# Keg_Cop_-_RJ45.net
KiCad netlist of a schematic drawn in EAGLE
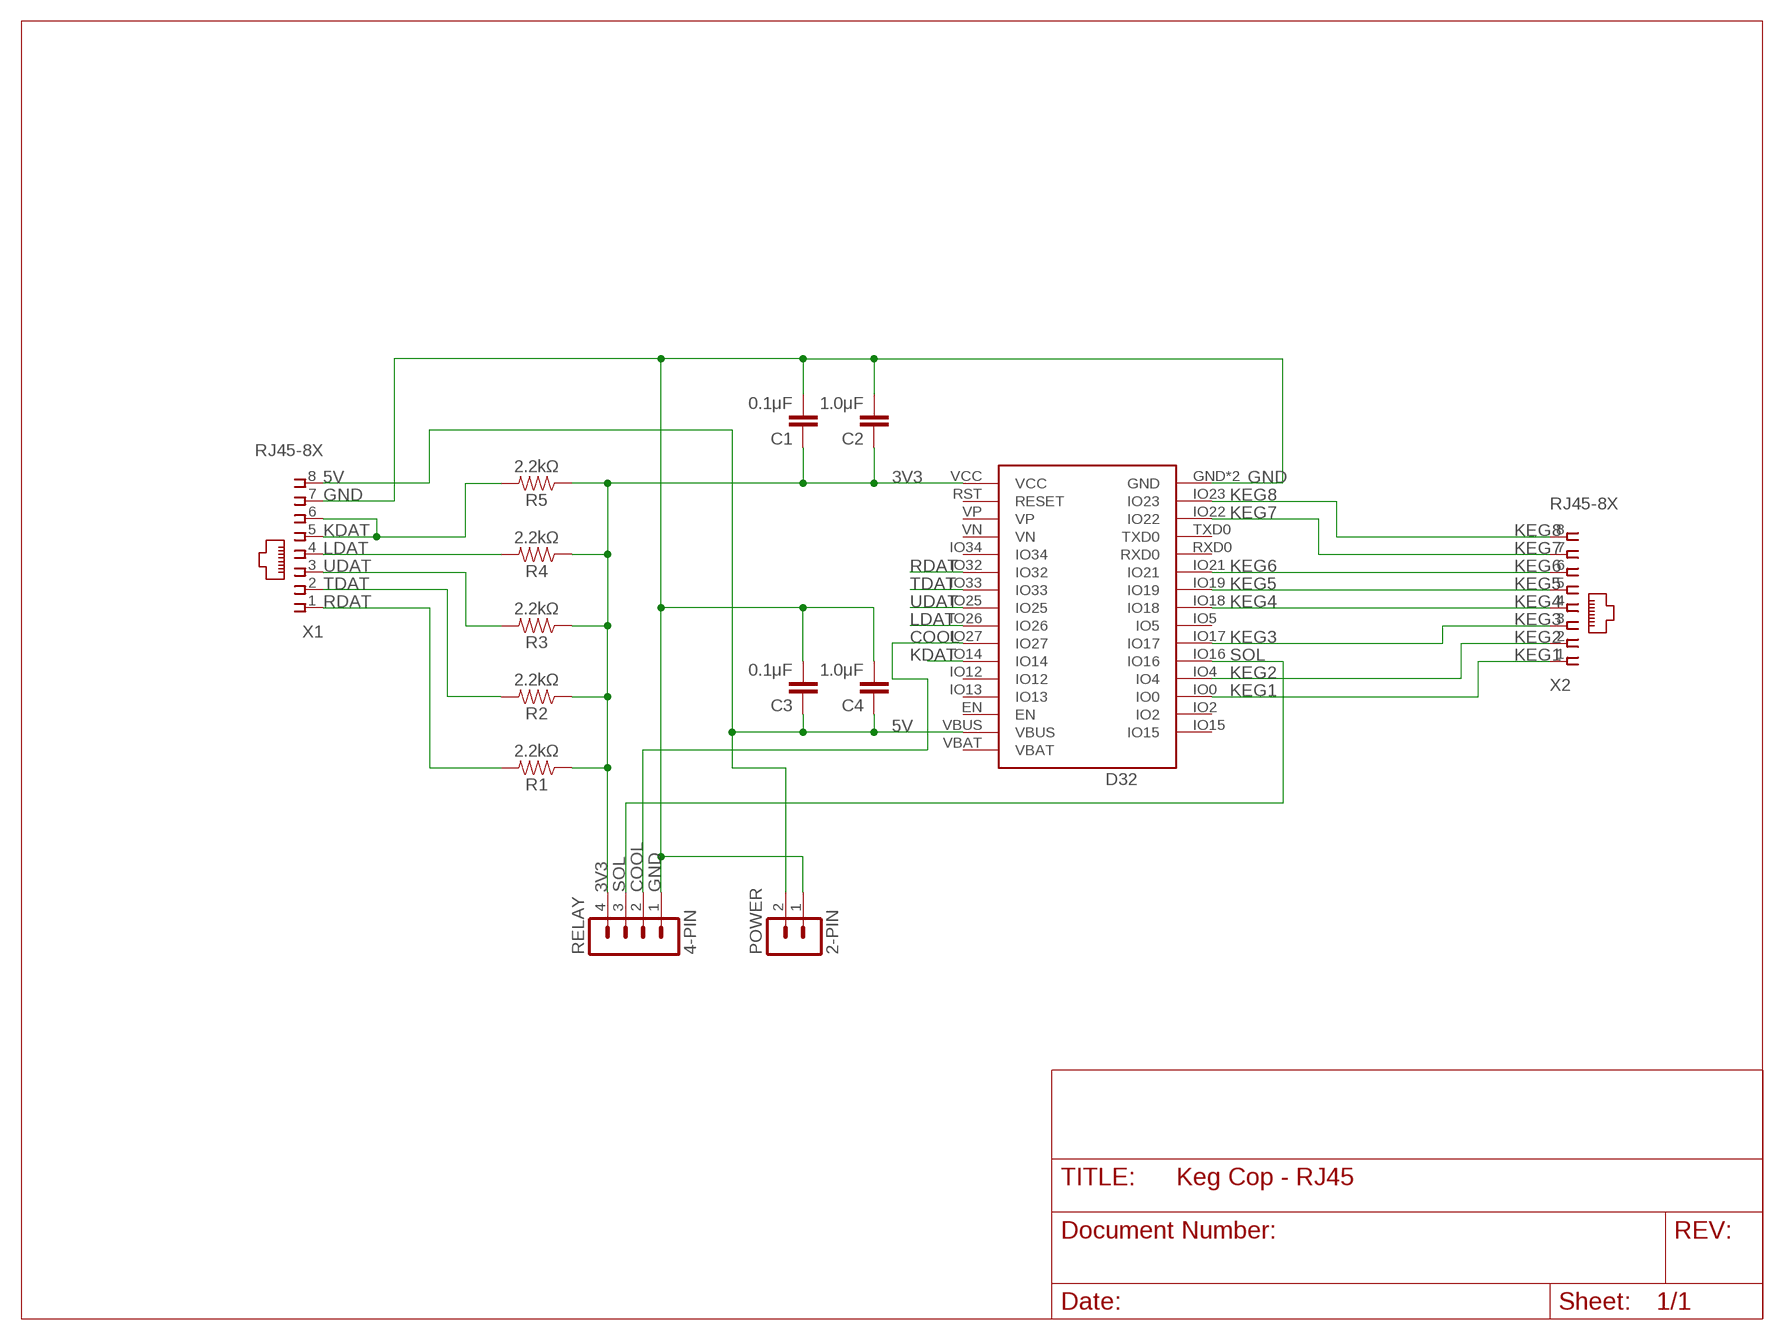
[diagram p0: schematic, sheet 1]

(export (version "E")
  (design (tool "Eeschema 10.0.6"))
  (components
    (comp (ref "C1")
      (value "0.1μF")
      (footprint "eagle-import:CAP_PTH-2.54")
      (libsource (lib "eagle-import") (part "CAP_CERAMIC_2.54"))
    )
    (comp (ref "C2")
      (value "1.0μF")
      (footprint "eagle-import:CAP_PTH-2.54")
      (libsource (lib "eagle-import") (part "CAP_CERAMIC_2.54"))
    )
    (comp (ref "C3")
      (value "0.1μF")
      (footprint "eagle-import:CAP_PTH-2.54")
      (libsource (lib "eagle-import") (part "CAP_CERAMIC_2.54"))
    )
    (comp (ref "C4")
      (value "1.0μF")
      (footprint "eagle-import:CAP_PTH-2.54")
      (libsource (lib "eagle-import") (part "CAP_CERAMIC_2.54"))
    )
    (comp (ref "D32")
      (value "Lolin D32")
      (footprint "eagle-import:D32_NO_BATT")
      (libsource (lib "eagle-import") (part "WEMOS-D32D32_NO_BATT"))
    )
    (comp (ref "POWER")
      (value "2-PIN")
      (footprint "eagle-import:HDR-2_VERT")
      (libsource (lib "eagle-import") (part "HDR-2"))
    )
    (comp (ref "R1")
      (value "2.2kΩ")
      (footprint "eagle-import:AXIAL-0.3")
      (libsource (lib "eagle-import") (part "RESISTORAXIAL-0.3"))
    )
    (comp (ref "R2")
      (value "2.2kΩ")
      (footprint "eagle-import:AXIAL-0.3")
      (libsource (lib "eagle-import") (part "RESISTORAXIAL-0.3"))
    )
    (comp (ref "R3")
      (value "2.2kΩ")
      (footprint "eagle-import:AXIAL-0.3")
      (libsource (lib "eagle-import") (part "RESISTORAXIAL-0.3"))
    )
    (comp (ref "R4")
      (value "2.2kΩ")
      (footprint "eagle-import:AXIAL-0.3")
      (libsource (lib "eagle-import") (part "RESISTORAXIAL-0.3"))
    )
    (comp (ref "R5")
      (value "2.2kΩ")
      (footprint "eagle-import:AXIAL-0.3")
      (libsource (lib "eagle-import") (part "RESISTORAXIAL-0.3"))
    )
    (comp (ref "RELAY")
      (value "4-PIN")
      (footprint "eagle-import:MA04-1")
      (libsource (lib "eagle-import") (part "MA04-1"))
    )
    (comp (ref "X1")
      (value "RJ45-8X")
      (footprint "eagle-import:RJ45-NO-SHIELD")
      (libsource (lib "eagle-import") (part "RJ45-8X"))
    )
    (comp (ref "X2")
      (value "RJ45-8X")
      (footprint "eagle-import:RJ45-NO-SHIELD")
      (libsource (lib "eagle-import") (part "RJ45-8X"))
    )
  )
  (nets
    (net (code "1") (name "/3V3") (class "Default")
      (node (ref "C1") (pin "1") (pinfunction "1_1") (pintype "passive"))
      (node (ref "C2") (pin "1") (pinfunction "1_1") (pintype "passive"))
      (node (ref "D32") (pin "VCC") (pinfunction "VCC_VCC") (pintype "power_in"))
      (node (ref "R1") (pin "P$1") (pinfunction "1_P$1") (pintype "passive"))
      (node (ref "R2") (pin "P$1") (pinfunction "1_P$1") (pintype "passive"))
      (node (ref "R3") (pin "P$1") (pinfunction "1_P$1") (pintype "passive"))
      (node (ref "R4") (pin "P$1") (pinfunction "1_P$1") (pintype "passive"))
      (node (ref "R5") (pin "P$1") (pinfunction "1_P$1") (pintype "passive"))
      (node (ref "RELAY") (pin "4") (pinfunction "4_4") (pintype "passive"))
    )
    (net (code "2") (name "/5V") (class "Default")
      (node (ref "C3") (pin "1") (pinfunction "1_1") (pintype "passive"))
      (node (ref "C4") (pin "1") (pinfunction "1_1") (pintype "passive"))
      (node (ref "D32") (pin "VBUS") (pinfunction "VBUS_VBUS") (pintype "bidirectional"))
      (node (ref "POWER") (pin "2") (pinfunction "2_2") (pintype "passive"))
      (node (ref "X1") (pin "8") (pinfunction "8_8") (pintype "passive"))
    )
    (net (code "3") (name "/COOL") (class "Default")
      (node (ref "D32") (pin "IO27") (pinfunction "IO27_IO27") (pintype "bidirectional"))
      (node (ref "RELAY") (pin "2") (pinfunction "2_2") (pintype "passive"))
    )
    (net (code "4") (name "/GND") (class "Default")
      (node (ref "C1") (pin "2") (pinfunction "2_2") (pintype "passive"))
      (node (ref "C2") (pin "2") (pinfunction "2_2") (pintype "passive"))
      (node (ref "C3") (pin "2") (pinfunction "2_2") (pintype "passive"))
      (node (ref "C4") (pin "2") (pinfunction "2_2") (pintype "passive"))
      (node (ref "D32") (pin "GND") (pinfunction "GND_GND") (pintype "power_in"))
      (node (ref "D32") (pin "GND2") (pinfunction "GND_GND2") (pintype "power_in"))
      (node (ref "POWER") (pin "1") (pinfunction "1_1") (pintype "passive"))
      (node (ref "RELAY") (pin "1") (pinfunction "1_1") (pintype "passive"))
      (node (ref "X1") (pin "7") (pinfunction "7_7") (pintype "passive"))
    )
    (net (code "5") (name "/KDAT") (class "Default")
      (node (ref "D32") (pin "IO14") (pinfunction "IO14_IO14") (pintype "bidirectional"))
      (node (ref "R5") (pin "P$2") (pinfunction "2_P$2") (pintype "passive"))
      (node (ref "X1") (pin "5") (pinfunction "5_5") (pintype "passive"))
      (node (ref "X1") (pin "6") (pinfunction "6_6") (pintype "passive"))
    )
    (net (code "6") (name "/KEG1") (class "Default")
      (node (ref "D32") (pin "IO0") (pinfunction "IO0_IO0") (pintype "bidirectional"))
      (node (ref "X2") (pin "1") (pinfunction "1_1") (pintype "passive"))
    )
    (net (code "7") (name "/KEG2") (class "Default")
      (node (ref "D32") (pin "IO4") (pinfunction "IO4_IO4") (pintype "bidirectional"))
      (node (ref "X2") (pin "2") (pinfunction "2_2") (pintype "passive"))
    )
    (net (code "8") (name "/KEG3") (class "Default")
      (node (ref "D32") (pin "IO17") (pinfunction "IO17_IO17") (pintype "bidirectional"))
      (node (ref "X2") (pin "3") (pinfunction "3_3") (pintype "passive"))
    )
    (net (code "9") (name "/KEG4") (class "Default")
      (node (ref "D32") (pin "IO18") (pinfunction "IO18_IO18") (pintype "bidirectional"))
      (node (ref "X2") (pin "4") (pinfunction "4_4") (pintype "passive"))
    )
    (net (code "10") (name "/KEG5") (class "Default")
      (node (ref "D32") (pin "IO19") (pinfunction "IO19_IO19") (pintype "bidirectional"))
      (node (ref "X2") (pin "5") (pinfunction "5_5") (pintype "passive"))
    )
    (net (code "11") (name "/KEG6") (class "Default")
      (node (ref "D32") (pin "IO21") (pinfunction "IO21_IO21") (pintype "bidirectional"))
      (node (ref "X2") (pin "6") (pinfunction "6_6") (pintype "passive"))
    )
    (net (code "12") (name "/KEG7") (class "Default")
      (node (ref "D32") (pin "IO22") (pinfunction "IO22_IO22") (pintype "bidirectional"))
      (node (ref "X2") (pin "7") (pinfunction "7_7") (pintype "passive"))
    )
    (net (code "13") (name "/KEG8") (class "Default")
      (node (ref "D32") (pin "IO23") (pinfunction "IO23_IO23") (pintype "bidirectional"))
      (node (ref "X2") (pin "8") (pinfunction "8_8") (pintype "passive"))
    )
    (net (code "14") (name "/LDAT") (class "Default")
      (node (ref "D32") (pin "IO26") (pinfunction "IO26_IO26") (pintype "bidirectional"))
      (node (ref "R4") (pin "P$2") (pinfunction "2_P$2") (pintype "passive"))
      (node (ref "X1") (pin "4") (pinfunction "4_4") (pintype "passive"))
    )
    (net (code "15") (name "/RDAT") (class "Default")
      (node (ref "D32") (pin "IO32") (pinfunction "IO32_IO32") (pintype "bidirectional"))
      (node (ref "R1") (pin "P$2") (pinfunction "2_P$2") (pintype "passive"))
      (node (ref "X1") (pin "1") (pinfunction "1_1") (pintype "passive"))
    )
    (net (code "16") (name "/SOL") (class "Default")
      (node (ref "D32") (pin "IO16") (pinfunction "IO16_IO16") (pintype "bidirectional"))
      (node (ref "RELAY") (pin "3") (pinfunction "3_3") (pintype "passive"))
    )
    (net (code "17") (name "/TDAT") (class "Default")
      (node (ref "D32") (pin "IO33") (pinfunction "IO33_IO33") (pintype "bidirectional"))
      (node (ref "R2") (pin "P$2") (pinfunction "2_P$2") (pintype "passive"))
      (node (ref "X1") (pin "2") (pinfunction "2_2") (pintype "passive"))
    )
    (net (code "18") (name "/UDAT") (class "Default")
      (node (ref "D32") (pin "IO25") (pinfunction "IO25_IO25") (pintype "bidirectional"))
      (node (ref "R3") (pin "P$2") (pinfunction "2_P$2") (pintype "passive"))
      (node (ref "X1") (pin "3") (pinfunction "3_3") (pintype "passive"))
    )
    (net (code "19") (name "unconnected-(D32-PadEN)") (class "Default")
      (node (ref "D32") (pin "EN") (pinfunction "EN_EN") (pintype "bidirectional"))
    )
    (net (code "20") (name "unconnected-(D32-PadIO2)") (class "Default")
      (node (ref "D32") (pin "IO2") (pinfunction "IO2_IO2") (pintype "bidirectional"))
    )
    (net (code "21") (name "unconnected-(D32-PadIO5)") (class "Default")
      (node (ref "D32") (pin "IO5") (pinfunction "IO5_IO5") (pintype "bidirectional"))
    )
    (net (code "22") (name "unconnected-(D32-PadIO12)") (class "Default")
      (node (ref "D32") (pin "IO12") (pinfunction "IO12_IO12") (pintype "bidirectional"))
    )
    (net (code "23") (name "unconnected-(D32-PadIO13)") (class "Default")
      (node (ref "D32") (pin "IO13") (pinfunction "IO13_IO13") (pintype "bidirectional"))
    )
    (net (code "24") (name "unconnected-(D32-PadIO15)") (class "Default")
      (node (ref "D32") (pin "IO15") (pinfunction "IO15_IO15") (pintype "bidirectional"))
    )
    (net (code "25") (name "unconnected-(D32-PadIO34)") (class "Default")
      (node (ref "D32") (pin "IO34") (pinfunction "IO34_IO34") (pintype "bidirectional"))
    )
    (net (code "26") (name "unconnected-(D32-PadRXD0)") (class "Default")
      (node (ref "D32") (pin "RXD0") (pinfunction "RXD0_RXD0") (pintype "input"))
    )
    (net (code "27") (name "unconnected-(D32-PadTXD0)") (class "Default")
      (node (ref "D32") (pin "TXD0") (pinfunction "TXD0_TXD0") (pintype "output"))
    )
    (net (code "28") (name "unconnected-(D32-PadVBAT)") (class "Default")
      (node (ref "D32") (pin "VBAT") (pinfunction "VBAT_VBAT") (pintype "bidirectional"))
    )
    (net (code "29") (name "unconnected-(D32-PadVN)") (class "Default")
      (node (ref "D32") (pin "VN") (pinfunction "VN_VN") (pintype "bidirectional"))
    )
    (net (code "30") (name "unconnected-(D32-PadVP)") (class "Default")
      (node (ref "D32") (pin "VP") (pinfunction "VP_VP") (pintype "bidirectional"))
    )
    (net (code "31") (name "unconnected-(D32-RESET-PadRST)") (class "Default")
      (node (ref "D32") (pin "RST") (pinfunction "RESET_RST") (pintype "bidirectional"))
    )
  )
)
